# STM32_microcontroller_power.net
KiCad netlist of a schematic drawn in Altium Designer
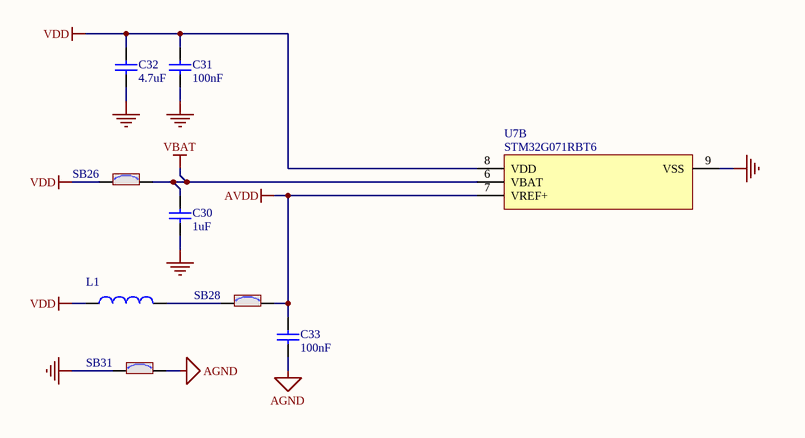
[diagram p0: STM32_microcontroller_power.SchDoc]

(export (version "E")
  (design (tool "Eeschema 10.0.6"))
  (components
    (comp (ref "C30")
      (value "1uF")
      (footprint "C0603")
      (description "Capacitor, MLCC, 1uF, 16V, X5R, 10%, 0603, T=0,8mm")
      (fields
        (field (name "INTERNAL_PART_NUMBER") "MCD-00010")
        (field (name "MANUFACTURER_PART_NUMBER") "CC0603KRX5R7BB105")
        (field (name "PROVIDED_BY") "Subcon")
      )
      (libsource (lib "MCD_PARTS_database") (part "Capacitor"))
    )
    (comp (ref "C31")
      (value "100nF")
      (footprint "C0603")
      (description "Capacitor, MLCC, 100nF, 16V, X7R, 10%, 0603, T=0,8mm")
      (fields
        (field (name "INTERNAL_PART_NUMBER") "MCD-00211")
        (field (name "MANUFACTURER_PART_NUMBER") "CC0603KRX7R7BB104")
        (field (name "PROVIDED_BY") "Subcon")
      )
      (libsource (lib "MCD_PARTS_database") (part "Capacitor"))
    )
    (comp (ref "C32")
      (value "4.7uF")
      (footprint "C0603")
      (description "Capacitor, MLCC, 4.7uF, 16V, X5R, 10%, 0603, T=0.8mm")
      (fields
        (field (name "INTERNAL_PART_NUMBER") "MCD-00009")
        (field (name "MANUFACTURER_PART_NUMBER") "CC0603KRX5R7BB475")
        (field (name "PROVIDED_BY") "subcon")
      )
      (libsource (lib "MCD_PARTS_database") (part "Capacitor"))
    )
    (comp (ref "C33")
      (value "100nF")
      (footprint "C0603")
      (description "Capacitor, MLCC, 100nF, 16V, X7R, 10%, 0603, T=0,8mm")
      (fields
        (field (name "INTERNAL_PART_NUMBER") "MCD-00211")
        (field (name "MANUFACTURER_PART_NUMBER") "CC0603KRX7R7BB104")
        (field (name "PROVIDED_BY") "Subcon")
      )
      (libsource (lib "MCD_PARTS_database") (part "Capacitor"))
    )
    (comp (ref "L1")
      (value "BEAD")
      (footprint "L0603")
      (description "SMD Chip ferrite bead, 600R@100MHz +/-25%, 350mA, 500mohm DC, 0603, T=0.8mm")
      (fields
        (field (name "INTERNAL_PART_NUMBER") "MCD-00047")
        (field (name "MANUFACTURER_PART_NUMBER") "FCM1608KF-601T03")
        (field (name "PROVIDED_BY") "Subcon")
      )
      (libsource (lib "MCD_PARTS_database") (part "BEAD"))
    )
    (comp (ref "SB26")
      (value "SB_ON")
      (footprint "SOLDER-BRIDGE_R0603-0R")
      (description "Solder Bridge ON")
      (fields (field (name "INTERNAL_PART_NUMBER") "MCD-00071") (field (name "PROVIDED_BY") "Subcon"))
      (libsource (lib "MCD_PARTS_database") (part "SB_ON"))
    )
    (comp (ref "SB28")
      (value "SB_ON")
      (footprint "SOLDER-BRIDGE_R0603-0R")
      (description "Solder Bridge ON")
      (fields (field (name "INTERNAL_PART_NUMBER") "MCD-00071") (field (name "PROVIDED_BY") "Subcon"))
      (libsource (lib "MCD_PARTS_database") (part "SB_ON"))
    )
    (comp (ref "SB31")
      (value "SB_ON")
      (footprint "SOLDER-BRIDGE_R0603-0R")
      (description "Solder Bridge ON")
      (fields (field (name "INTERNAL_PART_NUMBER") "MCD-00071") (field (name "PROVIDED_BY") "Subcon"))
      (libsource (lib "MCD_PARTS_database") (part "SB_ON"))
    )
    (comp (ref "U7")
      (value "STM32G071RBT6")
      (footprint "ICC_LQFP64_10X10_P050_SOCKET_YAMAICHI_IC149-064-069-B5")
      (description "Medium-density performance line ARM-based 32-bit MCU with 128KB Flash")
      (fields
        (field (name "INTERNAL_PART_NUMBER") "MCD-00662")
        (field (name "MANUFACTURER") "STMICROELECTRONICS")
        (field (name "PROVIDED_BY") "STM")
      )
      (libsource (lib "MCD_PARTS_database") (part "STM32G071RBT6"))
    )
  )
  (nets
    (net (code "1") (name "AGND") (class "Default")
      (node (ref "C33") (pin "1") (pinfunction "1_1") (pintype "passive"))
      (node (ref "SB31") (pin "2") (pinfunction "2_2") (pintype "passive"))
    )
    (net (code "2") (name "AVDD") (class "Default")
      (node (ref "C33") (pin "2") (pinfunction "2_2") (pintype "passive"))
      (node (ref "SB28") (pin "2") (pinfunction "2_2") (pintype "passive"))
      (node (ref "U7") (pin "7") (pinfunction "VREF+_7") (pintype "power_in"))
    )
    (net (code "3") (name "GND") (class "Default")
      (node (ref "C30") (pin "1") (pinfunction "1_1") (pintype "passive"))
      (node (ref "C31") (pin "1") (pinfunction "1_1") (pintype "passive"))
      (node (ref "C32") (pin "1") (pinfunction "1_1") (pintype "passive"))
      (node (ref "SB31") (pin "1") (pinfunction "1_1") (pintype "passive"))
      (node (ref "U7") (pin "9") (pinfunction "VSS_9") (pintype "passive"))
    )
    (net (code "4") (name "Net-(L1-Pad2)") (class "Default")
      (node (ref "L1") (pin "2") (pinfunction "2_2") (pintype "passive"))
      (node (ref "SB28") (pin "1") (pinfunction "1_1") (pintype "passive"))
    )
    (net (code "5") (name "VBAT") (class "Default")
      (node (ref "C30") (pin "2") (pinfunction "2_2") (pintype "passive"))
      (node (ref "SB26") (pin "2") (pinfunction "2_2") (pintype "passive"))
      (node (ref "U7") (pin "6") (pinfunction "VBAT_6") (pintype "power_in"))
    )
    (net (code "6") (name "VDD") (class "Default")
      (node (ref "C31") (pin "2") (pinfunction "2_2") (pintype "passive"))
      (node (ref "C32") (pin "2") (pinfunction "2_2") (pintype "passive"))
      (node (ref "L1") (pin "1") (pinfunction "1_1") (pintype "passive"))
      (node (ref "SB26") (pin "1") (pinfunction "1_1") (pintype "passive"))
      (node (ref "U7") (pin "8") (pinfunction "VDD_8") (pintype "power_in"))
    )
  )
)
